# Inverter_-_MOSFET.net
KiCad netlist of a schematic drawn in EAGLE
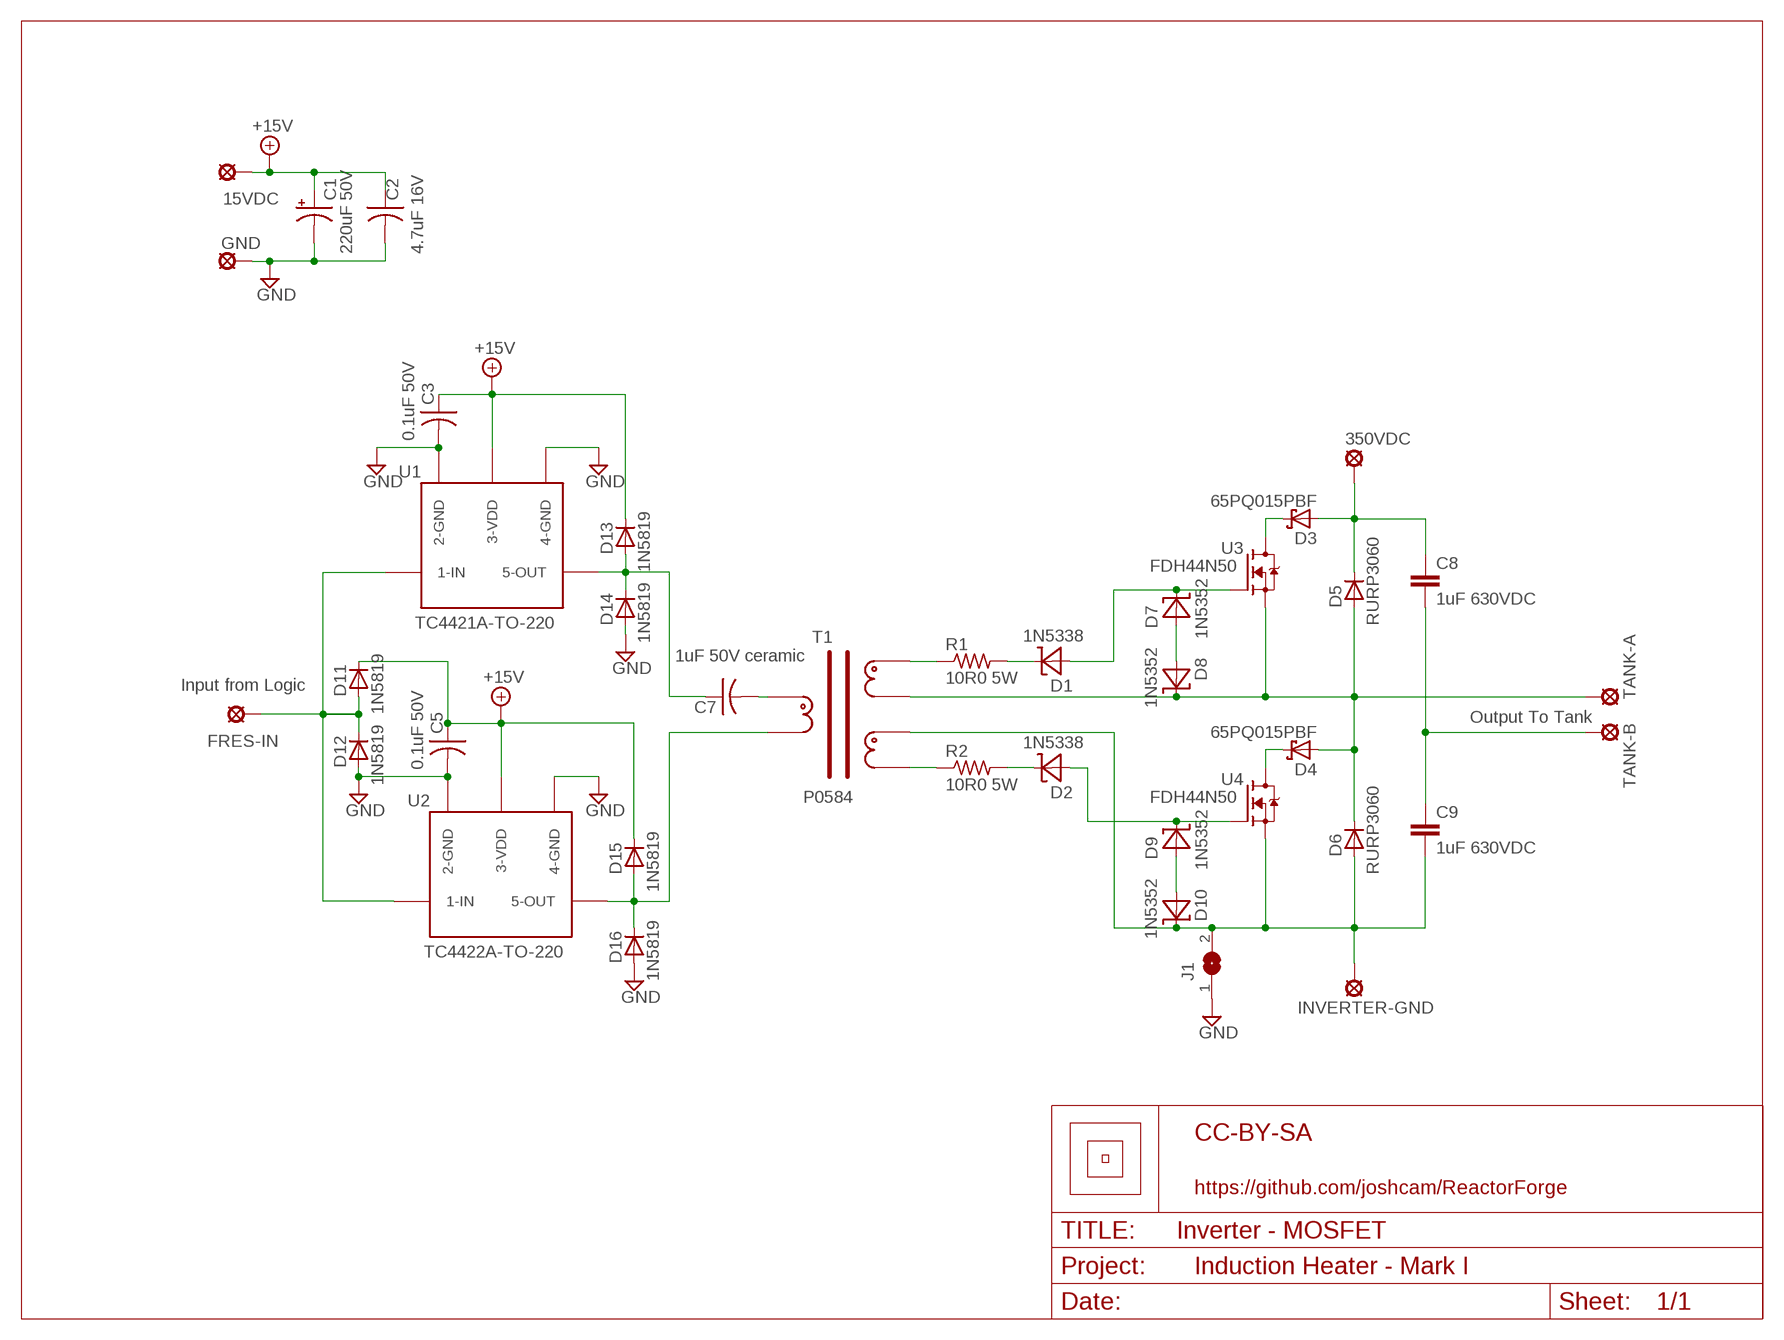
[diagram p0: schematic, sheet 1]

(export (version "E")
  (design (tool "Eeschema 10.0.6"))
  (components
    (comp (ref "15VDC")
      (value "SE14")
      (footprint "eagle-import:SE14")
      (libsource (lib "eagle-import") (part "SE14"))
    )
    (comp (ref "350VDC")
      (value "SE14")
      (footprint "eagle-import:SE14")
      (libsource (lib "eagle-import") (part "SE14"))
    )
    (comp (ref "C1")
      (value "220uF 50V")
      (footprint "eagle-import:E5-10,5")
      (libsource (lib "eagle-import") (part "CPOL-USE5-10.5"))
    )
    (comp (ref "C2")
      (value "4.7uF 16V")
      (footprint "eagle-import:C1206")
      (libsource (lib "eagle-import") (part "C-USC1206"))
    )
    (comp (ref "C3")
      (value "0.1uF 50V")
      (footprint "eagle-import:C1206")
      (libsource (lib "eagle-import") (part "C-USC1206"))
    )
    (comp (ref "C5")
      (value "0.1uF 50V")
      (footprint "eagle-import:C1206")
      (libsource (lib "eagle-import") (part "C-USC1206"))
    )
    (comp (ref "C7")
      (value "1uF 50V ceramic")
      (footprint "eagle-import:C1206")
      (libsource (lib "eagle-import") (part "C-USC1206"))
    )
    (comp (ref "C8")
      (value "1uF 630VDC")
      (footprint "eagle-import:CAPACITOR2.2-AXIAL")
      (libsource (lib "eagle-import") (part "MKP2000-1UF630V"))
    )
    (comp (ref "C9")
      (value "1uF 630VDC")
      (footprint "eagle-import:CAPACITOR2.2-AXIAL")
      (libsource (lib "eagle-import") (part "MKP2000-1UF630V"))
    )
    (comp (ref "D1")
      (value "1N5338")
      (footprint "eagle-import:DIODE.4-AXIAL")
      (libsource (lib "eagle-import") (part "1N5338"))
    )
    (comp (ref "D2")
      (value "1N5338")
      (footprint "eagle-import:DIODE.4-AXIAL")
      (libsource (lib "eagle-import") (part "1N5338"))
    )
    (comp (ref "D3")
      (value "65PQ015PBF")
      (footprint "eagle-import:TO-247AC-V")
      (libsource (lib "eagle-import") (part "65PQ015PBF"))
    )
    (comp (ref "D4")
      (value "65PQ015PBF")
      (footprint "eagle-import:TO-247AC-V")
      (libsource (lib "eagle-import") (part "65PQ015PBF"))
    )
    (comp (ref "D5")
      (value "RURP3060")
      (footprint "eagle-import:TO-220CA2-V")
      (libsource (lib "eagle-import") (part "RURP3060"))
    )
    (comp (ref "D6")
      (value "RURP3060")
      (footprint "eagle-import:TO-220CA2-V")
      (libsource (lib "eagle-import") (part "RURP3060"))
    )
    (comp (ref "D7")
      (value "1N5352")
      (footprint "eagle-import:DIODE.4-AXIAL")
      (libsource (lib "eagle-import") (part "1N5352"))
    )
    (comp (ref "D8")
      (value "1N5352")
      (footprint "eagle-import:DIODE.4-AXIAL")
      (libsource (lib "eagle-import") (part "1N5352"))
    )
    (comp (ref "D9")
      (value "1N5352")
      (footprint "eagle-import:DIODE.4-AXIAL")
      (libsource (lib "eagle-import") (part "1N5352"))
    )
    (comp (ref "D10")
      (value "1N5352")
      (footprint "eagle-import:DIODE.4-AXIAL")
      (libsource (lib "eagle-import") (part "1N5352"))
    )
    (comp (ref "D11")
      (value "1N5819")
      (footprint "eagle-import:DIODE.4-AXIAL")
      (libsource (lib "eagle-import") (part "1N5819"))
    )
    (comp (ref "D12")
      (value "1N5819")
      (footprint "eagle-import:DIODE.4-AXIAL")
      (libsource (lib "eagle-import") (part "1N5819"))
    )
    (comp (ref "D13")
      (value "1N5819")
      (footprint "eagle-import:DIODE.4-AXIAL")
      (libsource (lib "eagle-import") (part "1N5819"))
    )
    (comp (ref "D14")
      (value "1N5819")
      (footprint "eagle-import:DIODE.4-AXIAL")
      (libsource (lib "eagle-import") (part "1N5819"))
    )
    (comp (ref "D15")
      (value "1N5819")
      (footprint "eagle-import:DIODE.4-AXIAL")
      (libsource (lib "eagle-import") (part "1N5819"))
    )
    (comp (ref "D16")
      (value "1N5819")
      (footprint "eagle-import:DIODE.4-AXIAL")
      (libsource (lib "eagle-import") (part "1N5819"))
    )
    (comp (ref "FRES-IN")
      (value "SE14")
      (footprint "eagle-import:SE14")
      (libsource (lib "eagle-import") (part "SE14"))
    )
    (comp (ref "GND")
      (value "SE14")
      (footprint "eagle-import:SE14")
      (libsource (lib "eagle-import") (part "SE14"))
    )
    (comp (ref "INVERTER-GND")
      (value "SE14")
      (footprint "eagle-import:SE14")
      (libsource (lib "eagle-import") (part "SE14"))
    )
    (comp (ref "J1")
      (value "SJW")
      (footprint "eagle-import:SJW")
      (libsource (lib "eagle-import") (part "SJW"))
    )
    (comp (ref "R1")
      (value "10R0 5W")
      (footprint "eagle-import:P0817_22")
      (libsource (lib "eagle-import") (part "R-US_0817/22"))
    )
    (comp (ref "R2")
      (value "10R0 5W")
      (footprint "eagle-import:P0817_22")
      (libsource (lib "eagle-import") (part "R-US_0817/22"))
    )
    (comp (ref "T1")
      (value "P0584")
      (footprint "eagle-import:P0584")
      (libsource (lib "eagle-import") (part "P0584"))
    )
    (comp (ref "TANK-A")
      (value "SE14")
      (footprint "eagle-import:SE14")
      (libsource (lib "eagle-import") (part "SE14"))
    )
    (comp (ref "TANK-B")
      (value "SE14")
      (footprint "eagle-import:SE14")
      (libsource (lib "eagle-import") (part "SE14"))
    )
    (comp (ref "U1")
      (value "TC4421A-TO-220")
      (footprint "eagle-import:TO-220-8TAB-H")
      (libsource (lib "eagle-import") (part "TC4421A-TO-220"))
    )
    (comp (ref "U2")
      (value "TC4422A-TO-220")
      (footprint "eagle-import:TO-220-8TAB-H")
      (libsource (lib "eagle-import") (part "TC4422A-TO-220"))
    )
    (comp (ref "U3")
      (value "FDH44N50")
      (footprint "eagle-import:TO-247-V")
      (libsource (lib "eagle-import") (part "FDH44N50"))
    )
    (comp (ref "U4")
      (value "FDH44N50")
      (footprint "eagle-import:TO-247-V")
      (libsource (lib "eagle-import") (part "FDH44N50"))
    )
  )
  (nets
    (net (code "1") (name "+15V") (class "Default")
      (node (ref "15VDC") (pin "MP") (pinfunction "MP_MP") (pintype "passive"))
      (node (ref "C1") (pin "+") (pinfunction "+_+") (pintype "passive"))
      (node (ref "C2") (pin "1") (pinfunction "1_1") (pintype "passive"))
      (node (ref "C3") (pin "1") (pinfunction "1_1") (pintype "passive"))
      (node (ref "C5") (pin "1") (pinfunction "1_1") (pintype "passive"))
      (node (ref "D11") (pin "C") (pinfunction "C_C") (pintype "passive"))
      (node (ref "D13") (pin "C") (pinfunction "C_C") (pintype "passive"))
      (node (ref "D15") (pin "C") (pinfunction "C_C") (pintype "passive"))
      (node (ref "U1") (pin "3") (pinfunction "3-VDD_3") (pintype "power_in"))
      (node (ref "U1") (pin "TAB") (pinfunction "3-VDD_TAB") (pintype "power_in"))
      (node (ref "U2") (pin "3") (pinfunction "3-VDD_3") (pintype "power_in"))
      (node (ref "U2") (pin "TAB") (pinfunction "3-VDD_TAB") (pintype "power_in"))
    )
    (net (code "2") (name "GND") (class "Default")
      (node (ref "C1") (pin "-") (pinfunction "-_-") (pintype "passive"))
      (node (ref "C2") (pin "2") (pinfunction "2_2") (pintype "passive"))
      (node (ref "C3") (pin "2") (pinfunction "2_2") (pintype "passive"))
      (node (ref "C5") (pin "2") (pinfunction "2_2") (pintype "passive"))
      (node (ref "D12") (pin "A") (pinfunction "A_A") (pintype "passive"))
      (node (ref "D14") (pin "A") (pinfunction "A_A") (pintype "passive"))
      (node (ref "D16") (pin "A") (pinfunction "A_A") (pintype "passive"))
      (node (ref "GND") (pin "MP") (pinfunction "MP_MP") (pintype "passive"))
      (node (ref "J1") (pin "1") (pinfunction "1_1") (pintype "passive"))
      (node (ref "U1") (pin "2") (pinfunction "2-GND_2") (pintype "power_in"))
      (node (ref "U1") (pin "4") (pinfunction "4-GND_4") (pintype "power_in"))
      (node (ref "U2") (pin "2") (pinfunction "2-GND_2") (pintype "power_in"))
      (node (ref "U2") (pin "4") (pinfunction "4-GND_4") (pintype "power_in"))
    )
    (net (code "3") (name "Net-(C7-Pad2)") (class "Default")
      (node (ref "C7") (pin "2") (pinfunction "2_2") (pintype "passive"))
      (node (ref "T1") (pin "P$1") (pinfunction "P$1_P$1") (pintype "bidirectional"))
    )
    (net (code "4") (name "Net-(C8-1)") (class "Default")
      (node (ref "350VDC") (pin "MP") (pinfunction "MP_MP") (pintype "passive"))
      (node (ref "C8") (pin "P$1") (pinfunction "1_P$1") (pintype "passive"))
      (node (ref "D3") (pin "1") (pinfunction "A_1") (pintype "passive"))
      (node (ref "D3") (pin "3") (pinfunction "A_3") (pintype "passive"))
      (node (ref "D5") (pin "C") (pinfunction "C_C") (pintype "passive"))
    )
    (net (code "5") (name "Net-(C8-2)") (class "Default")
      (node (ref "C8") (pin "P$2") (pinfunction "2_P$2") (pintype "passive"))
      (node (ref "C9") (pin "P$1") (pinfunction "1_P$1") (pintype "passive"))
      (node (ref "TANK-B") (pin "MP") (pinfunction "MP_MP") (pintype "passive"))
    )
    (net (code "6") (name "Net-(C9-2)") (class "Default")
      (node (ref "C9") (pin "P$2") (pinfunction "2_P$2") (pintype "passive"))
      (node (ref "D10") (pin "C") (pinfunction "C_C") (pintype "passive"))
      (node (ref "D6") (pin "A") (pinfunction "A_A") (pintype "passive"))
      (node (ref "INVERTER-GND") (pin "MP") (pinfunction "MP_MP") (pintype "passive"))
      (node (ref "J1") (pin "2") (pinfunction "2_2") (pintype "passive"))
      (node (ref "T1") (pin "P$8") (pinfunction "P$8_P$8") (pintype "bidirectional"))
      (node (ref "U4") (pin "3") (pinfunction "S_3") (pintype "passive"))
    )
    (net (code "7") (name "Net-(D1-PadC)") (class "Default")
      (node (ref "D1") (pin "C") (pinfunction "C_C") (pintype "passive"))
      (node (ref "R1") (pin "2") (pinfunction "2_2") (pintype "passive"))
    )
    (net (code "8") (name "Net-(D2-PadC)") (class "Default")
      (node (ref "D2") (pin "C") (pinfunction "C_C") (pintype "passive"))
      (node (ref "R2") (pin "2") (pinfunction "2_2") (pintype "passive"))
    )
    (net (code "9") (name "Net-(D3-C)") (class "Default")
      (node (ref "D3") (pin "2") (pinfunction "C_2") (pintype "passive"))
      (node (ref "U3") (pin "2") (pinfunction "D_2") (pintype "passive"))
    )
    (net (code "10") (name "Net-(D4-C)") (class "Default")
      (node (ref "D4") (pin "2") (pinfunction "C_2") (pintype "passive"))
      (node (ref "U4") (pin "2") (pinfunction "D_2") (pintype "passive"))
    )
    (net (code "11") (name "Net-(D7-PadA)") (class "Default")
      (node (ref "D7") (pin "A") (pinfunction "A_A") (pintype "passive"))
      (node (ref "D8") (pin "A") (pinfunction "A_A") (pintype "passive"))
    )
    (net (code "12") (name "Net-(D10-PadA)") (class "Default")
      (node (ref "D10") (pin "A") (pinfunction "A_A") (pintype "passive"))
      (node (ref "D9") (pin "A") (pinfunction "A_A") (pintype "passive"))
    )
    (net (code "13") (name "Net-(R1-Pad1)") (class "Default")
      (node (ref "R1") (pin "1") (pinfunction "1_1") (pintype "passive"))
      (node (ref "T1") (pin "P$3") (pinfunction "P$3_P$3") (pintype "bidirectional"))
    )
    (net (code "14") (name "Net-(R2-Pad1)") (class "Default")
      (node (ref "R2") (pin "1") (pinfunction "1_1") (pintype "passive"))
      (node (ref "T1") (pin "P$7") (pinfunction "P$7_P$7") (pintype "bidirectional"))
    )
    (net (code "15") (name "Net-(U1-1-IN)") (class "Default")
      (node (ref "D11") (pin "A") (pinfunction "A_A") (pintype "passive"))
      (node (ref "D12") (pin "C") (pinfunction "C_C") (pintype "passive"))
      (node (ref "FRES-IN") (pin "MP") (pinfunction "MP_MP") (pintype "passive"))
      (node (ref "U1") (pin "1") (pinfunction "1-IN_1") (pintype "bidirectional"))
      (node (ref "U2") (pin "1") (pinfunction "1-IN_1") (pintype "bidirectional"))
    )
    (net (code "16") (name "Net-(U1-5-OUT)") (class "Default")
      (node (ref "C7") (pin "1") (pinfunction "1_1") (pintype "passive"))
      (node (ref "D13") (pin "A") (pinfunction "A_A") (pintype "passive"))
      (node (ref "D14") (pin "C") (pinfunction "C_C") (pintype "passive"))
      (node (ref "U1") (pin "5") (pinfunction "5-OUT_5") (pintype "bidirectional"))
    )
    (net (code "17") (name "Net-(U2-5-OUT)") (class "Default")
      (node (ref "D15") (pin "A") (pinfunction "A_A") (pintype "passive"))
      (node (ref "D16") (pin "C") (pinfunction "C_C") (pintype "passive"))
      (node (ref "T1") (pin "P$10") (pinfunction "P$10_P$10") (pintype "bidirectional"))
      (node (ref "U2") (pin "5") (pinfunction "5-OUT_5") (pintype "bidirectional"))
    )
    (net (code "18") (name "Net-(U3-G)") (class "Default")
      (node (ref "D1") (pin "A") (pinfunction "A_A") (pintype "passive"))
      (node (ref "D7") (pin "C") (pinfunction "C_C") (pintype "passive"))
      (node (ref "U3") (pin "1") (pinfunction "G_1") (pintype "passive"))
    )
    (net (code "19") (name "Net-(U3-S)") (class "Default")
      (node (ref "D4") (pin "1") (pinfunction "A_1") (pintype "passive"))
      (node (ref "D4") (pin "3") (pinfunction "A_3") (pintype "passive"))
      (node (ref "D5") (pin "A") (pinfunction "A_A") (pintype "passive"))
      (node (ref "D6") (pin "C") (pinfunction "C_C") (pintype "passive"))
      (node (ref "D8") (pin "C") (pinfunction "C_C") (pintype "passive"))
      (node (ref "T1") (pin "P$4") (pinfunction "P$4_P$4") (pintype "bidirectional"))
      (node (ref "TANK-A") (pin "MP") (pinfunction "MP_MP") (pintype "passive"))
      (node (ref "U3") (pin "3") (pinfunction "S_3") (pintype "passive"))
    )
    (net (code "20") (name "Net-(U4-G)") (class "Default")
      (node (ref "D2") (pin "A") (pinfunction "A_A") (pintype "passive"))
      (node (ref "D9") (pin "C") (pinfunction "C_C") (pintype "passive"))
      (node (ref "U4") (pin "1") (pinfunction "G_1") (pintype "passive"))
    )
  )
)
